# v2_full_project.net
KiCad netlist of a schematic drawn in EasyEDA Pro
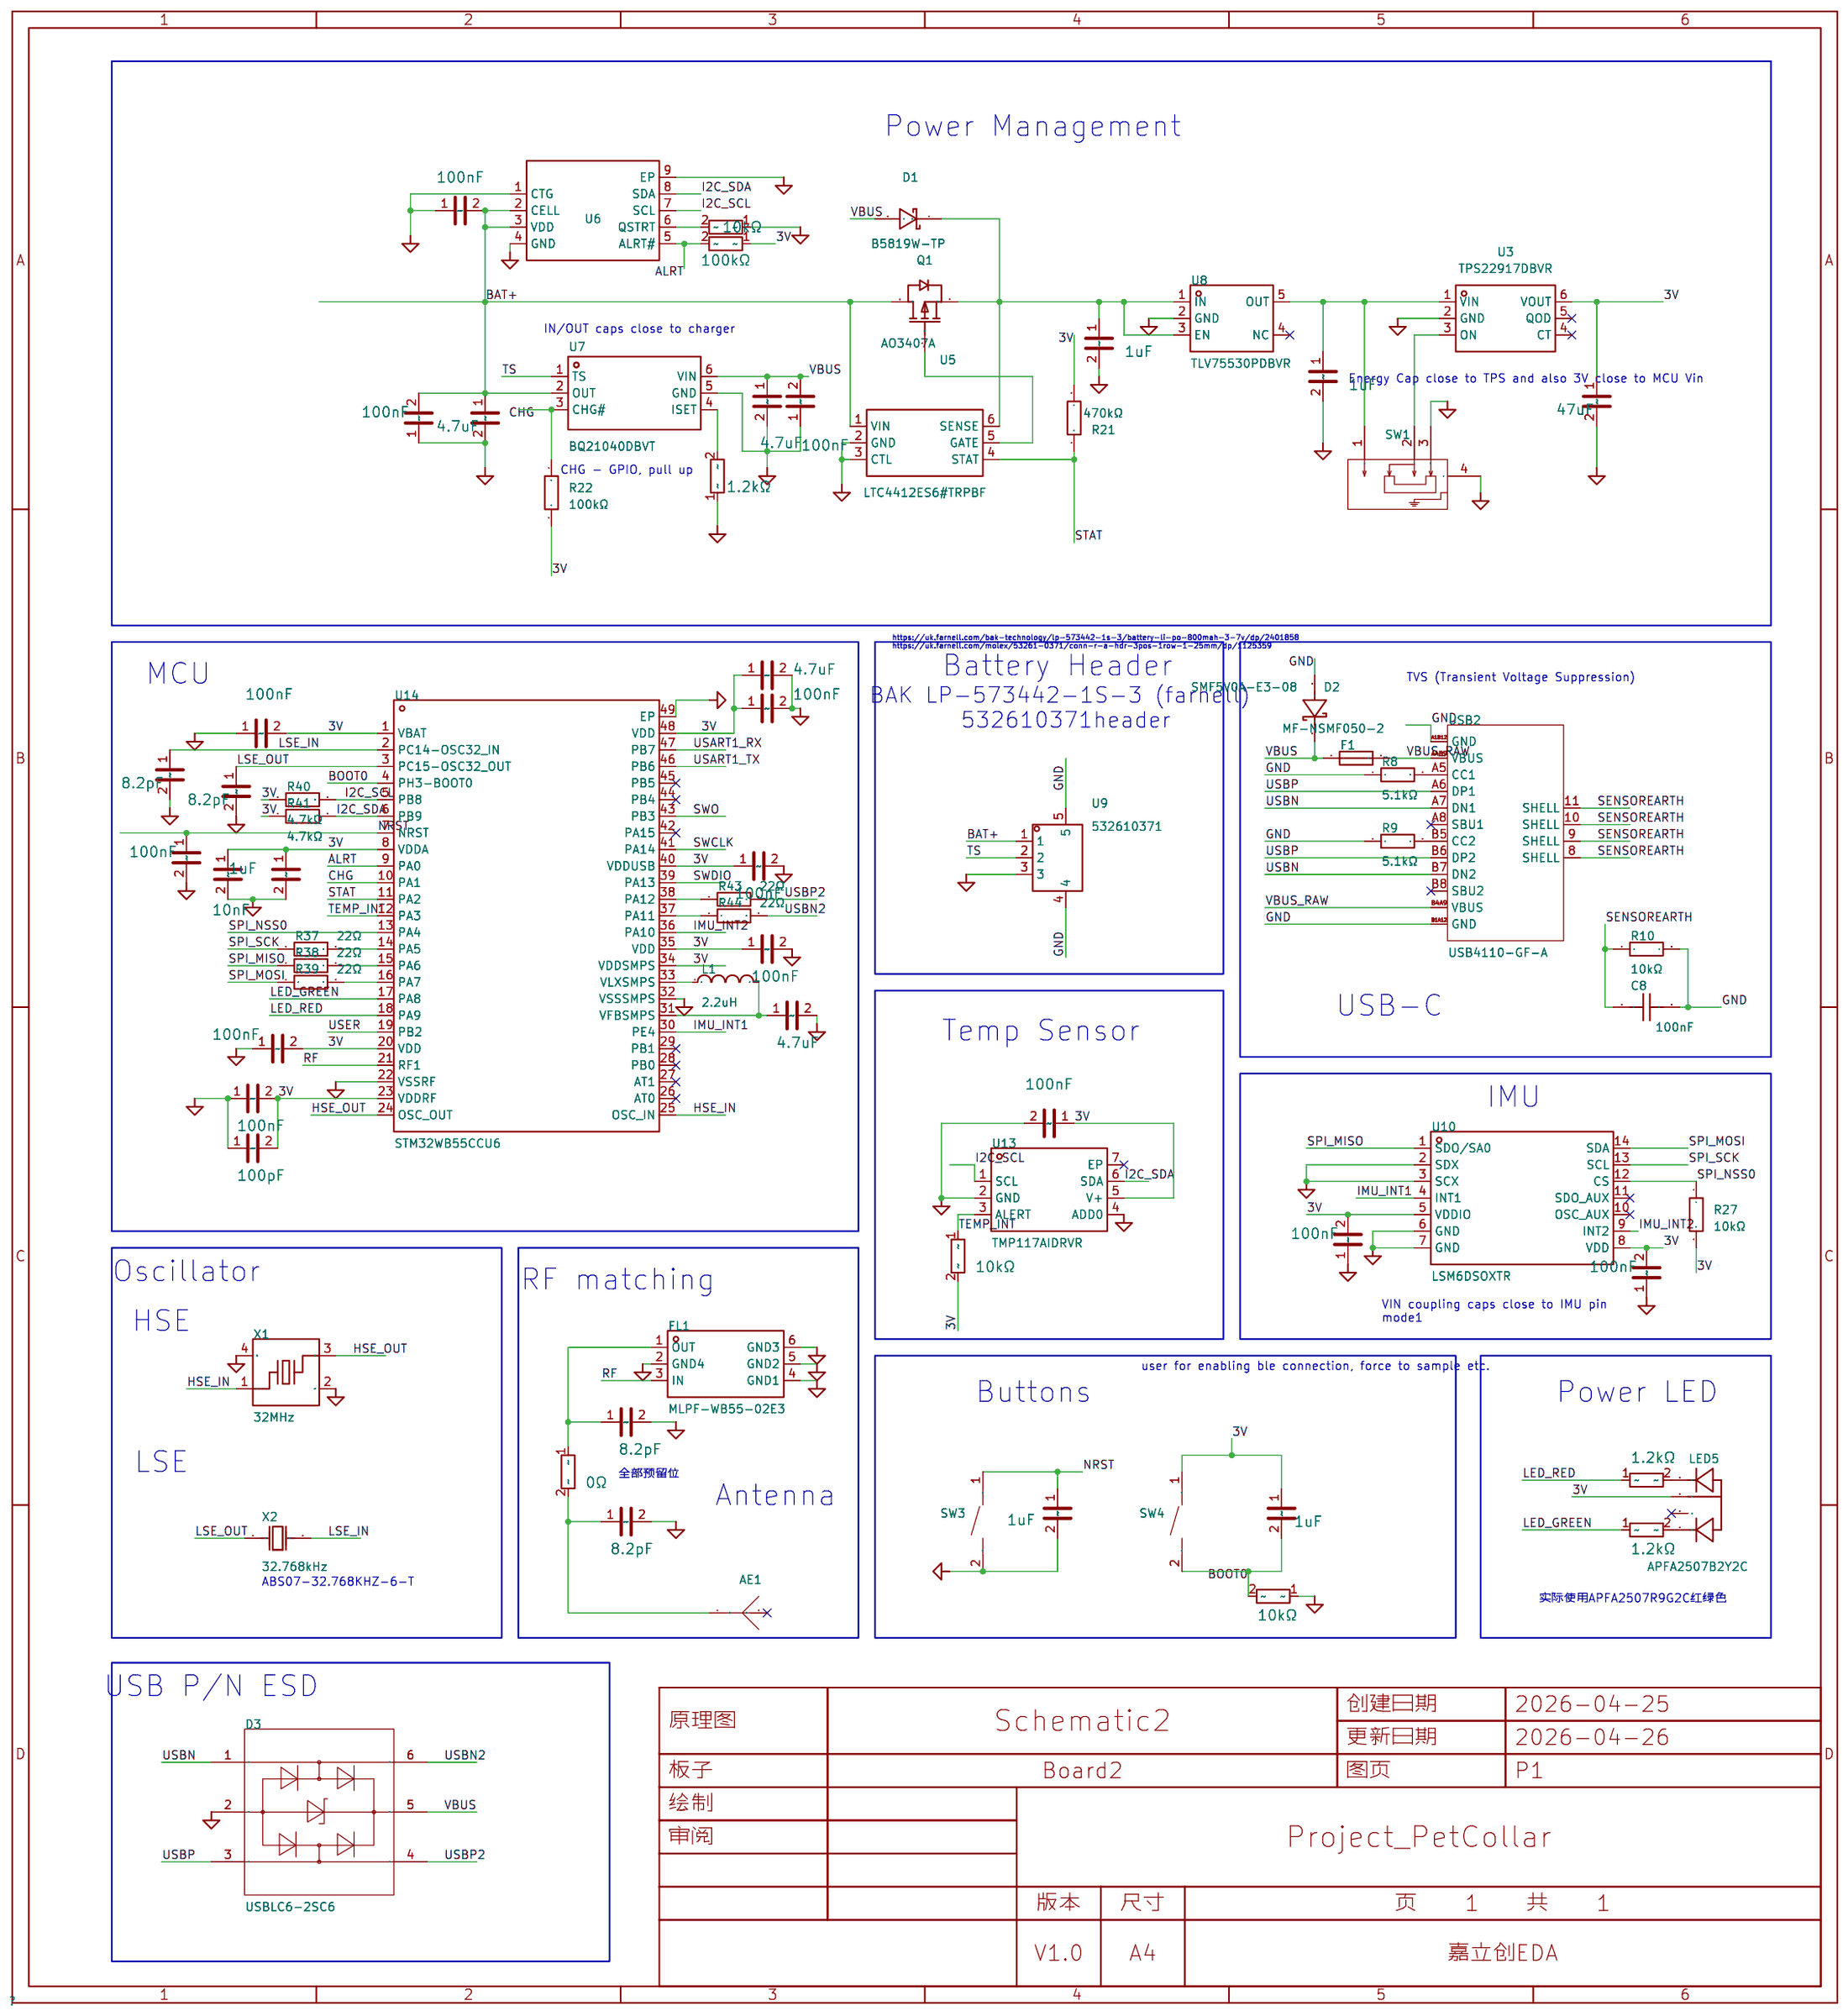
[diagram p0: schematic sheet]

(export (version "E")
  (design (tool "Eeschema 10.0.6"))
  (components
    (comp (ref "AE1")
      (value "2450AT18A100E")
      (footprint "easyedapro:ANT-SMD_L3.2-W1.6")
      (fields (field (name "Manufacturer") "JOHANSON(约翰逊)"))
      (libsource (lib "easyedapro") (part "2450AT18A100E"))
    )
    (comp (ref "C1")
      (value "100nF")
      (description "容值:100nF;精度:±10%;额定电压:50V;温度系数:X7R;")
      (fields
        (field (name "Manufacturer Part") "CL10B104KB8NNNC")
        (field (name "Manufacturer") "SAMSUNG(三星)")
      )
      (libsource (lib "easyedapro") (part "Device_C"))
    )
    (comp (ref "C2")
      (value "1uF")
      (description "容值:1uF;精度:±10%;额定电压:25V;温度系数:X7R;")
      (fields
        (field (name "Manufacturer Part") "CL10B105KA8NNNC")
        (field (name "Manufacturer") "SAMSUNG(三星)")
      )
      (libsource (lib "easyedapro") (part "Device_C"))
    )
    (comp (ref "C3")
      (value "1uF")
      (description "容值:1uF;精度:±10%;额定电压:25V;温度系数:X7R;")
      (fields
        (field (name "Manufacturer Part") "CL10B105KA8NNNC")
        (field (name "Manufacturer") "SAMSUNG(三星)")
      )
      (libsource (lib "easyedapro") (part "Device_C"))
    )
    (comp (ref "C5")
      (value "47uF")
      (description "容值:47uF;精度:±20%;额定电压:6.3V;温度系数:X5R;")
      (fields
        (field (name "Manufacturer Part") "CL21A476MQYNNNE")
        (field (name "Manufacturer") "SAMSUNG(三星)")
      )
      (libsource (lib "easyedapro") (part "Device_C"))
    )
    (comp (ref "C8")
      (value "100nF")
      (fields
        (field (name "Manufacturer Part") "CL10B104KB8NNNC")
        (field (name "Manufacturer") "SAMSUNG(三星)")
      )
      (libsource (lib "easyedapro") (part "Capacitance"))
    )
    (comp (ref "C19")
      (value "1uF")
      (description "容值:1uF;精度:±10%;额定电压:25V;温度系数:X7R;")
      (fields
        (field (name "Manufacturer Part") "CL10B105KA8NNNC")
        (field (name "Manufacturer") "SAMSUNG(三星)")
      )
      (libsource (lib "easyedapro") (part "Device_C"))
    )
    (comp (ref "C23")
      (value "4.7uF")
      (description "容值:4.7uF;精度:±10%;额定电压:16V;温度系数:X5R;")
      (fields
        (field (name "Manufacturer Part") "CL10A475KO8NNNC")
        (field (name "Manufacturer") "SAMSUNG(三星)")
      )
      (libsource (lib "easyedapro") (part "Device_C"))
    )
    (comp (ref "C24")
      (value "4.7uF")
      (description "容值:4.7uF;精度:±10%;额定电压:16V;温度系数:X5R;")
      (fields
        (field (name "Manufacturer Part") "CL10A475KO8NNNC")
        (field (name "Manufacturer") "SAMSUNG(三星)")
      )
      (libsource (lib "easyedapro") (part "Device_C"))
    )
    (comp (ref "C25")
      (value "100nF")
      (description "容值:100nF;精度:±10%;额定电压:50V;温度系数:X7R;")
      (fields
        (field (name "Manufacturer Part") "CL10B104KB8NNNC")
        (field (name "Manufacturer") "SAMSUNG(三星)")
      )
      (libsource (lib "easyedapro") (part "Device_C"))
    )
    (comp (ref "C26")
      (value "100nF")
      (description "容值:100nF;精度:±10%;额定电压:50V;温度系数:X7R;")
      (fields
        (field (name "Manufacturer Part") "CL10B104KB8NNNC")
        (field (name "Manufacturer") "SAMSUNG(三星)")
      )
      (libsource (lib "easyedapro") (part "Device_C"))
    )
    (comp (ref "C27")
      (value "100nF")
      (description "容值:100nF;精度:±10%;额定电压:50V;温度系数:X7R;")
      (fields
        (field (name "Manufacturer Part") "CL10B104KB8NNNC")
        (field (name "Manufacturer") "SAMSUNG(三星)")
      )
      (libsource (lib "easyedapro") (part "Device_C"))
    )
    (comp (ref "C28")
      (value "100nF")
      (description "容值:100nF;精度:±10%;额定电压:50V;温度系数:X7R;")
      (fields
        (field (name "Manufacturer Part") "CL10B104KB8NNNC")
        (field (name "Manufacturer") "SAMSUNG(三星)")
      )
      (libsource (lib "easyedapro") (part "Device_C"))
    )
    (comp (ref "C41")
      (value "100nF")
      (description "容值:100nF;精度:±10%;额定电压:50V;温度系数:X7R;")
      (fields
        (field (name "Manufacturer Part") "CL10B104KB8NNNC")
        (field (name "Manufacturer") "SAMSUNG(三星)")
      )
      (libsource (lib "easyedapro") (part "Device_C"))
    )
    (comp (ref "C42")
      (value "8.2pF")
      (description "容值:8.2pF;额定电压:50V;材质(温度系数):C0G;")
      (fields
        (field (name "Manufacturer Part") "GJM1555C1H8R2BB01D")
        (field (name "Manufacturer") "muRata(村田)")
      )
      (libsource (lib "easyedapro") (part "Device_C"))
    )
    (comp (ref "C43")
      (value "8.2pF")
      (description "容值:8.2pF;额定电压:50V;材质(温度系数):C0G;")
      (fields
        (field (name "Manufacturer Part") "GJM1555C1H8R2BB01D")
        (field (name "Manufacturer") "muRata(村田)")
      )
      (libsource (lib "easyedapro") (part "Device_C"))
    )
    (comp (ref "C46")
      (value "4.7uF")
      (description "容值:4.7uF;精度:±10%;额定电压:16V;温度系数:X5R;")
      (fields
        (field (name "Manufacturer Part") "CL10A475KO8NNNC")
        (field (name "Manufacturer") "SAMSUNG(三星)")
      )
      (libsource (lib "easyedapro") (part "Device_C"))
    )
    (comp (ref "C49")
      (value "100nF")
      (description "容值:100nF;精度:±10%;额定电压:50V;温度系数:X7R;")
      (fields
        (field (name "Manufacturer Part") "CL10B104KB8NNNC")
        (field (name "Manufacturer") "SAMSUNG(三星)")
      )
      (libsource (lib "easyedapro") (part "Device_C"))
    )
    (comp (ref "C50")
      (value "100nF")
      (description "容值:100nF;精度:±10%;额定电压:50V;温度系数:X7R;")
      (fields
        (field (name "Manufacturer Part") "CL10B104KB8NNNC")
        (field (name "Manufacturer") "SAMSUNG(三星)")
      )
      (libsource (lib "easyedapro") (part "Device_C"))
    )
    (comp (ref "C51")
      (value "100nF")
      (description "容值:100nF;精度:±10%;额定电压:50V;温度系数:X7R;")
      (fields
        (field (name "Manufacturer Part") "CL10B104KB8NNNC")
        (field (name "Manufacturer") "SAMSUNG(三星)")
      )
      (libsource (lib "easyedapro") (part "Device_C"))
    )
    (comp (ref "C52")
      (value "4.7uF")
      (description "容值:4.7uF;精度:±10%;额定电压:16V;温度系数:X5R;")
      (fields
        (field (name "Manufacturer Part") "CL10A475KO8NNNC")
        (field (name "Manufacturer") "SAMSUNG(三星)")
      )
      (libsource (lib "easyedapro") (part "Device_C"))
    )
    (comp (ref "C53")
      (value "10nF")
      (description "容值:10nF;精度:±5%;额定电压:50V;材质(温度系数):C0G;")
      (fields
        (field (name "Manufacturer Part") "GRM1885C1H103JA01D")
        (field (name "Manufacturer") "muRata(村田)")
      )
      (libsource (lib "easyedapro") (part "Device_C"))
    )
    (comp (ref "C54")
      (value "1uF")
      (description "容值:1uF;精度:±10%;额定电压:25V;温度系数:X7R;")
      (fields
        (field (name "Manufacturer Part") "CL10B105KA8NNNC")
        (field (name "Manufacturer") "SAMSUNG(三星)")
      )
      (libsource (lib "easyedapro") (part "Device_C"))
    )
    (comp (ref "C55")
      (value "100nF")
      (description "容值:100nF;精度:±10%;额定电压:50V;温度系数:X7R;")
      (fields
        (field (name "Manufacturer Part") "CL10B104KB8NNNC")
        (field (name "Manufacturer") "SAMSUNG(三星)")
      )
      (libsource (lib "easyedapro") (part "Device_C"))
    )
    (comp (ref "C56")
      (value "100nF")
      (description "容值:100nF;精度:±10%;额定电压:50V;温度系数:X7R;")
      (fields
        (field (name "Manufacturer Part") "CL10B104KB8NNNC")
        (field (name "Manufacturer") "SAMSUNG(三星)")
      )
      (libsource (lib "easyedapro") (part "Device_C"))
    )
    (comp (ref "C57")
      (value "100pF")
      (description "容值:100pF;精度:±5%;额定电压:50V;温度系数:C0G;")
      (fields
        (field (name "Manufacturer Part") "CL10C101JB8NNNC")
        (field (name "Manufacturer") "SAMSUNG(三星)")
      )
      (libsource (lib "easyedapro") (part "Device_C"))
    )
    (comp (ref "C58")
      (value "100nF")
      (description "容值:100nF;精度:±10%;额定电压:50V;温度系数:X7R;")
      (fields
        (field (name "Manufacturer Part") "CL10B104KB8NNNC")
        (field (name "Manufacturer") "SAMSUNG(三星)")
      )
      (libsource (lib "easyedapro") (part "Device_C"))
    )
    (comp (ref "C59")
      (value "100nF")
      (description "容值:100nF;精度:±10%;额定电压:50V;温度系数:X7R;")
      (fields
        (field (name "Manufacturer Part") "CL10B104KB8NNNC")
        (field (name "Manufacturer") "SAMSUNG(三星)")
      )
      (libsource (lib "easyedapro") (part "Device_C"))
    )
    (comp (ref "C60")
      (value "1uF")
      (description "容值:1uF;精度:±10%;额定电压:25V;温度系数:X7R;")
      (fields
        (field (name "Manufacturer Part") "CL10B105KA8NNNC")
        (field (name "Manufacturer") "SAMSUNG(三星)")
      )
      (libsource (lib "easyedapro") (part "Device_C"))
    )
    (comp (ref "C61")
      (value "8.2pF")
      (description "容值:8.2pF;额定电压:50V;材质(温度系数):C0G;")
      (fields
        (field (name "Manufacturer Part") "GJM1555C1H8R2BB01D")
        (field (name "Manufacturer") "muRata(村田)")
      )
      (libsource (lib "easyedapro") (part "Device_C"))
    )
    (comp (ref "C62")
      (value "8.2pF")
      (description "容值:8.2pF;额定电压:50V;材质(温度系数):C0G;")
      (fields
        (field (name "Manufacturer Part") "GJM1555C1H8R2BB01D")
        (field (name "Manufacturer") "muRata(村田)")
      )
      (libsource (lib "easyedapro") (part "Device_C"))
    )
    (comp (ref "D1")
      (value "B5819W-TP")
      (footprint "easyedapro:SOD-123_L2.8-W1.8-LS3.7-RD")
      (description "二极管配置:-;正向压降(Vf):600mV@1A;直流反向耐压(Vr):40V;整流电流:1A;")
      (fields (field (name "Manufacturer") "MCC(美微科)"))
      (libsource (lib "easyedapro") (part "B5819W-TP"))
    )
    (comp (ref "D2")
      (value "SMF5V0A-E3-08")
      (footprint "easyedapro:SMF_L2.8-W1.8-LS3.7-RD")
      (fields (field (name "Manufacturer") "VISHAY(威世)"))
      (libsource (lib "easyedapro") (part "SMF5V0A-E3-08"))
    )
    (comp (ref "D3")
      (value "USBLC6-2SC6")
      (footprint "easyedapro:SOT-23-6_L2.9-W1.6-P0.95-LS2.8-BL")
      (description "极性:单向;反向截止电压(Vrwm):5.25V;钳位电压:17V;峰值脉冲电流(Ipp):5A;击穿电压:6V;")
      (fields (field (name "Manufacturer") "ST(意法半导体)"))
      (libsource (lib "easyedapro") (part "USBLC6-2SC6"))
    )
    (comp (ref "F1")
      (value "MF-NSMF050-2")
      (footprint "easyedapro:F1206")
      (fields (field (name "Manufacturer") "BOURNS"))
      (libsource (lib "easyedapro") (part "MF-NSMF050-2"))
    )
    (comp (ref "FL1")
      (value "MLPF-WB55-02E3")
      (footprint "easyedapro:FILTER-SMD_6P-L1.6-W1.0-P0.50-BL")
      (fields (field (name "Manufacturer") "ST(意法半导体)"))
      (libsource (lib "easyedapro") (part "MLPF-WB55-02E3"))
    )
    (comp (ref "L1")
      (value "2.2uH")
      (footprint "easyedapro:L1008")
      (fields
        (field (name "Manufacturer Part") "1239AS-H-2R2M=P2")
        (field (name "Manufacturer") "muRata(村田)")
      )
      (libsource (lib "easyedapro") (part "1239AS-H-2R2M=P2"))
    )
    (comp (ref "LED5")
      (value "APFA2507B2Y2C")
      (footprint "easyedapro:LED-SMD_4P-L2.5-W1.0_APFA2507LQBDSEEZGKC")
      (fields (field (name "Manufacturer") "Kingbright"))
      (libsource (lib "easyedapro") (part "APFA2507B2Y2C"))
    )
    (comp (ref "Q1")
      (value "AO3407A")
      (footprint "easyedapro:SOT-23-3_L2.9-W1.6-P1.90-LS2.8-BR")
      (fields (field (name "Manufacturer") "AOS"))
      (libsource (lib "easyedapro") (part "AO3407A"))
    )
    (comp (ref "R1")
      (value "10kΩ")
      (description "电阻类型:厚膜电阻;阻值:10kΩ;精度:±1%;功率:100mW;最大工作电压:75V;温度系数:±100ppm/℃;")
      (fields (field (name "Manufacturer Part") "RC0603FR-0710KL") (field (name "Manufacturer") "YAGEO(国巨)"))
      (libsource (lib "easyedapro") (part "Device_R"))
    )
    (comp (ref "R2")
      (value "100kΩ")
      (description "电阻类型:厚膜电阻;阻值:100kΩ;精度:±1%;功率:100mW;最大工作电压:75V;温度系数:±100ppm/℃;")
      (fields (field (name "Manufacturer Part") "RC0603FR-07100KL") (field (name "Manufacturer") "YAGEO(国巨)"))
      (libsource (lib "easyedapro") (part "Device_R"))
    )
    (comp (ref "R8")
      (value "5.1kΩ")
      (fields (field (name "Manufacturer Part") "FRC0603F5102TS") (field (name "Manufacturer") "FOJAN(富捷)"))
      (libsource (lib "easyedapro") (part "电阻"))
    )
    (comp (ref "R9")
      (value "5.1kΩ")
      (fields (field (name "Manufacturer Part") "FRC0603F5102TS") (field (name "Manufacturer") "FOJAN(富捷)"))
      (libsource (lib "easyedapro") (part "电阻"))
    )
    (comp (ref "R10")
      (value "10kΩ")
      (fields (field (name "Manufacturer Part") "RC0603FR-0710KL") (field (name "Manufacturer") "YAGEO(国巨)"))
      (libsource (lib "easyedapro") (part "电阻"))
    )
    (comp (ref "R20")
      (value "1.2kΩ")
      (fields (field (name "Manufacturer Part") "RC0603FR-071K2L") (field (name "Manufacturer") "YAGEO(国巨)"))
      (libsource (lib "easyedapro") (part "Device_R"))
    )
    (comp (ref "R21")
      (value "470kΩ")
      (fields (field (name "Manufacturer Part") "FRC0603F4703TS") (field (name "Manufacturer") "FOJAN(富捷)"))
      (libsource (lib "easyedapro") (part "电阻"))
    )
    (comp (ref "R22")
      (value "100kΩ")
      (fields (field (name "Manufacturer Part") "RC0603FR-07100KL") (field (name "Manufacturer") "YAGEO(国巨)"))
      (libsource (lib "easyedapro") (part "电阻"))
    )
    (comp (ref "R27")
      (value "10kΩ")
      (fields (field (name "Manufacturer Part") "RC0603FR-0710KL") (field (name "Manufacturer") "YAGEO(国巨)"))
      (libsource (lib "easyedapro") (part "电阻"))
    )
    (comp (ref "R35")
      (value "10kΩ")
      (description "电阻类型:厚膜电阻;阻值:10kΩ;精度:±1%;功率:100mW;最大工作电压:75V;温度系数:±100ppm/℃;")
      (fields (field (name "Manufacturer Part") "RC0603FR-0710KL") (field (name "Manufacturer") "YAGEO(国巨)"))
      (libsource (lib "easyedapro") (part "Device_R"))
    )
    (comp (ref "R36")
      (value "0Ω")
      (description "电阻类型:厚膜电阻;阻值:0Ω;精度:±1%;功率:62.5mW;工作电压:50V;温度系数:-;")
      (fields (field (name "Manufacturer Part") "RC0402FR-070RL") (field (name "Manufacturer") "YAGEO(国巨)"))
      (libsource (lib "easyedapro") (part "Device_R"))
    )
    (comp (ref "R37")
      (value "22Ω")
      (fields (field (name "Manufacturer Part") "FRC0603J220 TS") (field (name "Manufacturer") "FOJAN(富捷)"))
      (libsource (lib "easyedapro") (part "电阻"))
    )
    (comp (ref "R38")
      (value "22Ω")
      (fields (field (name "Manufacturer Part") "FRC0603J220 TS") (field (name "Manufacturer") "FOJAN(富捷)"))
      (libsource (lib "easyedapro") (part "电阻"))
    )
    (comp (ref "R39")
      (value "22Ω")
      (fields (field (name "Manufacturer Part") "FRC0603J220 TS") (field (name "Manufacturer") "FOJAN(富捷)"))
      (libsource (lib "easyedapro") (part "电阻"))
    )
    (comp (ref "R40")
      (value "4.7kΩ")
      (fields (field (name "Manufacturer Part") "RC0603FR-074K7L") (field (name "Manufacturer") "YAGEO(国巨)"))
      (libsource (lib "easyedapro") (part "电阻"))
    )
    (comp (ref "R41")
      (value "4.7kΩ")
      (fields (field (name "Manufacturer Part") "RC0603FR-074K7L") (field (name "Manufacturer") "YAGEO(国巨)"))
      (libsource (lib "easyedapro") (part "电阻"))
    )
    (comp (ref "R42")
      (value "10kΩ")
      (description "电阻类型:厚膜电阻;阻值:10kΩ;精度:±1%;功率:100mW;最大工作电压:75V;温度系数:±100ppm/℃;")
      (fields (field (name "Manufacturer Part") "RC0603FR-0710KL") (field (name "Manufacturer") "YAGEO(国巨)"))
      (libsource (lib "easyedapro") (part "Device_R"))
    )
    (comp (ref "R43")
      (value "22Ω")
      (fields (field (name "Manufacturer Part") "FRC0603J220 TS") (field (name "Manufacturer") "FOJAN(富捷)"))
      (libsource (lib "easyedapro") (part "电阻"))
    )
    (comp (ref "R44")
      (value "22Ω")
      (fields (field (name "Manufacturer Part") "FRC0603J220 TS") (field (name "Manufacturer") "FOJAN(富捷)"))
      (libsource (lib "easyedapro") (part "电阻"))
    )
    (comp (ref "R45")
      (value "1.2kΩ")
      (fields (field (name "Manufacturer Part") "RC0603FR-071K2L") (field (name "Manufacturer") "YAGEO(国巨)"))
      (libsource (lib "easyedapro") (part "Device_R"))
    )
    (comp (ref "R46")
      (value "1.2kΩ")
      (fields (field (name "Manufacturer Part") "RC0603FR-071K2L") (field (name "Manufacturer") "YAGEO(国巨)"))
      (libsource (lib "easyedapro") (part "Device_R"))
    )
    (comp (ref "SW1")
      (value "MSK12C02")
      (footprint "easyedapro:SW-TH_MSK12C02")
      (fields (field (name "Manufacturer") "SHOU HAN(首韩)"))
      (libsource (lib "easyedapro") (part "MSK12C02"))
    )
    (comp (ref "SW3")
      (value "TS-1088-AR02016")
      (footprint "easyedapro:SW-SMD_L3.9-W3.0-P4.45")
      (fields (field (name "Manufacturer") "XUNPU(讯普)"))
      (libsource (lib "easyedapro") (part "TS-1088-AR02016"))
    )
    (comp (ref "SW4")
      (value "TS-1088-AR02016")
      (footprint "easyedapro:SW-SMD_L3.9-W3.0-P4.45")
      (fields (field (name "Manufacturer") "XUNPU(讯普)"))
      (libsource (lib "easyedapro") (part "TS-1088-AR02016"))
    )
    (comp (ref "U3")
      (value "TPS22917DBVR")
      (footprint "easyedapro:SOT-23-6_L2.9-W1.6-P0.95-LS2.8-BR")
      (description "类型:负载开关;通道数:1;输入控制逻辑:高电平有效;最大连续电流:2A;工作电压:0V~5.5V;导通电阻:80mΩ;")
      (fields (field (name "Manufacturer") "TI(德州仪器)"))
      (libsource (lib "easyedapro") (part "TPS22917DBVR"))
    )
    (comp (ref "U5")
      (value "LTC4412ES6#TRPBF")
      (footprint "easyedapro:TSOT-23-6_L2.9-W1.6-P0.95-LS2.8-BR")
      (description "负载类型:MOSFET;工作电压:2.5V~28V;")
      (fields (field (name "Manufacturer") "ADI(亚德诺)"))
      (libsource (lib "easyedapro") (part "LTC4412ES6#TRPBF"))
    )
    (comp (ref "U6")
      (value "MAX17048G+T10")
      (footprint "easyedapro:TDFN-8_L2.0-W2.0-P0.50-BL-EP1.2")
      (description "工作电压:2.5V~4.5V;电池类型:锂离子/聚合物;电池节数:1;")
      (fields (field (name "Manufacturer") "ADI(亚德诺)/MAXIM(美信)"))
      (libsource (lib "easyedapro") (part "MAX17048G+T10"))
    )
    (comp (ref "U7")
      (value "BQ21040DBVT")
      (footprint "easyedapro:SOT-23-6_L2.9-W1.6-P0.95-LS2.8-BR")
      (fields (field (name "Manufacturer") "TI(德州仪器)"))
      (libsource (lib "easyedapro") (part "BQ21040DBVT"))
    )
    (comp (ref "U8")
      (value "TLV75530PDBVR")
      (footprint "easyedapro:SOT-23-5_L3.0-W1.7-P0.95-LS2.8-BR")
      (fields (field (name "Manufacturer") "TI(德州仪器)"))
      (libsource (lib "easyedapro") (part "TLV75530PDBVR"))
    )
    (comp (ref "U9")
      (value "532610371")
      (footprint "easyedapro:CONN-TH_532610371")
      (fields (field (name "Manufacturer") "MOLEX"))
      (libsource (lib "easyedapro") (part "532610371"))
    )
    (comp (ref "U10")
      (value "LSM6DSOXTR")
      (footprint "easyedapro:LGA-14L_L3.0-W2.5-P0.50-TL")
      (fields (field (name "Manufacturer") "ST(意法半导体)"))
      (libsource (lib "easyedapro") (part "LSM6DSOXTR"))
    )
    (comp (ref "U13")
      (value "TMP117AIDRVR")
      (footprint "easyedapro:WSON-6_L2.0-W2.0-P0.65-TL-EP")
      (fields (field (name "Manufacturer") "TI(德州仪器)"))
      (libsource (lib "easyedapro") (part "TMP117AIDRVR"))
    )
    (comp (ref "U14")
      (value "STM32WB55CCU6")
      (footprint "easyedapro:VQFN-48_L7.0-W7.0-P0.50-BL-EP5.5")
      (fields (field (name "Manufacturer") "ST(意法半导体)"))
      (libsource (lib "easyedapro") (part "STM32WB55CCU6"))
    )
    (comp (ref "USB2")
      (value "USB4110-GF-A")
      (footprint "easyedapro:USB-C-SMD_TYPE-C-16P-USB4110-GF-A")
      (description "连接器类型:Type-C;协议标准:USB 2.0;公母:母;安装方式:卧贴;端口数量:1;额定电流 - 电源:5A;工作温度:-40°C~+85°C;")
      (fields (field (name "Manufacturer") "GCT"))
      (libsource (lib "easyedapro") (part "USB4110-GF-A"))
    )
    (comp (ref "X1")
      (value "32MHz")
      (footprint "easyedapro:CRYSTAL-SMD_4P-L2.0-W1.6-BL")
      (fields
        (field (name "Manufacturer Part") "NX2016SA-32MHZ-EXS00A-CS06654")
        (field (name "Manufacturer") "NDK")
      )
      (libsource (lib "easyedapro") (part "NX2016SA-32MHZ-EXS00A-CS06654"))
    )
    (comp (ref "X2")
      (value "32.768kHz")
      (footprint "easyedapro:CRYSTAL-SMD_L3.2-W1.5-2")
      (fields
        (field (name "Manufacturer Part") "ABS07-32.768KHZ-6-T")
        (field (name "Manufacturer") "ABRACON")
      )
      (libsource (lib "easyedapro") (part "ABS07-32.768KHZ-6-T"))
    )
  )
  (nets
    (net (code "1") (name "/3V") (class "Default")
      (node (ref "C27") (pin "2") (pinfunction "~_2") (pintype "unspecified"))
      (node (ref "C28") (pin "2") (pinfunction "~_2") (pintype "unspecified"))
      (node (ref "C41") (pin "1") (pinfunction "~_1") (pintype "unspecified"))
      (node (ref "C49") (pin "2") (pinfunction "~_2") (pintype "unspecified"))
      (node (ref "C5") (pin "1") (pinfunction "~_1") (pintype "unspecified"))
      (node (ref "C50") (pin "1") (pinfunction "~_1") (pintype "unspecified"))
      (node (ref "C51") (pin "1") (pinfunction "~_1") (pintype "unspecified"))
      (node (ref "C52") (pin "1") (pinfunction "~_1") (pintype "unspecified"))
      (node (ref "C53") (pin "1") (pinfunction "~_1") (pintype "unspecified"))
      (node (ref "C54") (pin "1") (pinfunction "~_1") (pintype "unspecified"))
      (node (ref "C55") (pin "1") (pinfunction "~_1") (pintype "unspecified"))
      (node (ref "C56") (pin "2") (pinfunction "~_2") (pintype "unspecified"))
      (node (ref "C57") (pin "2") (pinfunction "~_2") (pintype "unspecified"))
      (node (ref "C58") (pin "2") (pinfunction "~_2") (pintype "unspecified"))
      (node (ref "C60") (pin "1") (pinfunction "~_1") (pintype "unspecified"))
      (node (ref "LED5") (pin "2") (pinfunction "2_2") (pintype "unspecified"))
      (node (ref "R2") (pin "1") (pinfunction "~_1") (pintype "unspecified"))
      (node (ref "R21") (pin "2") (pinfunction "2_2") (pintype "input"))
      (node (ref "R22") (pin "2") (pinfunction "2_2") (pintype "input"))
      (node (ref "R27") (pin "2") (pinfunction "2_2") (pintype "input"))
      (node (ref "R35") (pin "2") (pinfunction "~_2") (pintype "unspecified"))
      (node (ref "R40") (pin "1") (pinfunction "1_1") (pintype "input"))
      (node (ref "R41") (pin "1") (pinfunction "1_1") (pintype "input"))
      (node (ref "SW4") (pin "1") (pinfunction "1_1") (pintype "unspecified"))
      (node (ref "U10") (pin "5") (pinfunction "VDDIO_5") (pintype "unspecified"))
      (node (ref "U10") (pin "8") (pinfunction "VDD_8") (pintype "unspecified"))
      (node (ref "U13") (pin "5") (pinfunction "V+_5") (pintype "unspecified"))
      (node (ref "U14") (pin "1") (pinfunction "VBAT_1") (pintype "unspecified"))
      (node (ref "U14") (pin "20") (pinfunction "VDD_20") (pintype "unspecified"))
      (node (ref "U14") (pin "23") (pinfunction "VDDRF_23") (pintype "unspecified"))
      (node (ref "U14") (pin "34") (pinfunction "VDDSMPS_34") (pintype "unspecified"))
      (node (ref "U14") (pin "35") (pinfunction "VDD_35") (pintype "unspecified"))
      (node (ref "U14") (pin "40") (pinfunction "VDDUSB_40") (pintype "unspecified"))
      (node (ref "U14") (pin "48") (pinfunction "VDD_48") (pintype "unspecified"))
      (node (ref "U14") (pin "8") (pinfunction "VDDA_8") (pintype "unspecified"))
      (node (ref "U3") (pin "6") (pinfunction "VOUT_6") (pintype "unspecified"))
    )
    (net (code "2") (name "/ALRT") (class "Default")
      (node (ref "R2") (pin "2") (pinfunction "~_2") (pintype "unspecified"))
      (node (ref "U14") (pin "9") (pinfunction "PA0_9") (pintype "unspecified"))
      (node (ref "U6") (pin "5") (pinfunction "ALRT#_5") (pintype "unspecified"))
    )
    (net (code "3") (name "/BAT+") (class "Default")
      (node (ref "C1") (pin "2") (pinfunction "~_2") (pintype "unspecified"))
      (node (ref "C24") (pin "1") (pinfunction "~_1") (pintype "unspecified"))
      (node (ref "C25") (pin "2") (pinfunction "~_2") (pintype "unspecified"))
      (node (ref "Q1") (pin "3") (pinfunction "D_3") (pintype "unspecified"))
      (node (ref "U5") (pin "1") (pinfunction "VIN_1") (pintype "unspecified"))
      (node (ref "U6") (pin "2") (pinfunction "CELL_2") (pintype "unspecified"))
      (node (ref "U6") (pin "3") (pinfunction "VDD_3") (pintype "unspecified"))
      (node (ref "U7") (pin "2") (pinfunction "OUT_2") (pintype "unspecified"))
      (node (ref "U9") (pin "1") (pinfunction "1_1") (pintype "unspecified"))
    )
    (net (code "4") (name "/BOOT0") (class "Default")
      (node (ref "C60") (pin "2") (pinfunction "~_2") (pintype "unspecified"))
      (node (ref "R42") (pin "2") (pinfunction "~_2") (pintype "unspecified"))
      (node (ref "SW4") (pin "2") (pinfunction "2_2") (pintype "unspecified"))
      (node (ref "U14") (pin "4") (pinfunction "PH3-BOOT0_4") (pintype "unspecified"))
    )
    (net (code "5") (name "/CHG") (class "Default")
      (node (ref "R22") (pin "1") (pinfunction "1_1") (pintype "input"))
      (node (ref "U14") (pin "10") (pinfunction "PA1_10") (pintype "unspecified"))
      (node (ref "U7") (pin "3") (pinfunction "CHG#_3") (pintype "unspecified"))
    )
    (net (code "6") (name "/HSE_IN") (class "Default")
      (node (ref "U14") (pin "25") (pinfunction "OSC_IN_25") (pintype "unspecified"))
      (node (ref "X1") (pin "1") (pinfunction "1_1") (pintype "input"))
    )
    (net (code "7") (name "/HSE_OUT") (class "Default")
      (node (ref "U14") (pin "24") (pinfunction "OSC_OUT_24") (pintype "unspecified"))
      (node (ref "X1") (pin "3") (pinfunction "3_3") (pintype "input"))
    )
    (net (code "8") (name "/I2C_SCL") (class "Default")
      (node (ref "R40") (pin "2") (pinfunction "2_2") (pintype "input"))
      (node (ref "U13") (pin "1") (pinfunction "SCL_1") (pintype "unspecified"))
      (node (ref "U14") (pin "5") (pinfunction "PB8_5") (pintype "unspecified"))
      (node (ref "U6") (pin "7") (pinfunction "SCL_7") (pintype "unspecified"))
    )
    (net (code "9") (name "/I2C_SDA") (class "Default")
      (node (ref "R41") (pin "2") (pinfunction "2_2") (pintype "input"))
      (node (ref "U13") (pin "6") (pinfunction "SDA_6") (pintype "unspecified"))
      (node (ref "U14") (pin "6") (pinfunction "PB9_6") (pintype "unspecified"))
      (node (ref "U6") (pin "8") (pinfunction "SDA_8") (pintype "unspecified"))
    )
    (net (code "10") (name "/IMU_INT1") (class "Default")
      (node (ref "U10") (pin "4") (pinfunction "INT1_4") (pintype "unspecified"))
      (node (ref "U14") (pin "30") (pinfunction "PE4_30") (pintype "unspecified"))
    )
    (net (code "11") (name "/IMU_INT2") (class "Default")
      (node (ref "U10") (pin "9") (pinfunction "INT2_9") (pintype "unspecified"))
      (node (ref "U14") (pin "36") (pinfunction "PA10_36") (pintype "unspecified"))
    )
    (net (code "12") (name "/LED_GREEN") (class "Default")
      (node (ref "R46") (pin "1") (pinfunction "~_1") (pintype "unspecified"))
      (node (ref "U14") (pin "17") (pinfunction "PA8_17") (pintype "unspecified"))
    )
    (net (code "13") (name "/LED_RED") (class "Default")
      (node (ref "R45") (pin "1") (pinfunction "~_1") (pintype "unspecified"))
      (node (ref "U14") (pin "18") (pinfunction "PA9_18") (pintype "unspecified"))
    )
    (net (code "14") (name "/LSE_IN") (class "Default")
      (node (ref "C42") (pin "1") (pinfunction "~_1") (pintype "unspecified"))
      (node (ref "U14") (pin "2") (pinfunction "PC14-OSC32_IN_2") (pintype "unspecified"))
      (node (ref "X2") (pin "2") (pinfunction "OSC2_2") (pintype "input"))
    )
    (net (code "15") (name "/LSE_OUT") (class "Default")
      (node (ref "C43") (pin "1") (pinfunction "~_1") (pintype "unspecified"))
      (node (ref "U14") (pin "3") (pinfunction "PC15-OSC32_OUT_3") (pintype "unspecified"))
      (node (ref "X2") (pin "1") (pinfunction "OSC1_1") (pintype "input"))
    )
    (net (code "16") (name "/NRST") (class "Default")
      (node (ref "C19") (pin "1") (pinfunction "~_1") (pintype "unspecified"))
      (node (ref "C59") (pin "1") (pinfunction "~_1") (pintype "unspecified"))
      (node (ref "SW3") (pin "1") (pinfunction "1_1") (pintype "unspecified"))
      (node (ref "U14") (pin "7") (pinfunction "NRST_7") (pintype "unspecified"))
    )
    (net (code "17") (name "/RF") (class "Default")
      (node (ref "FL1") (pin "3") (pinfunction "IN_3") (pintype "unspecified"))
      (node (ref "U14") (pin "21") (pinfunction "RF1_21") (pintype "unspecified"))
    )
    (net (code "18") (name "/SENSOREARTH") (class "Default")
      (node (ref "C8") (pin "1") (pinfunction "1_1") (pintype "input"))
      (node (ref "R10") (pin "1") (pinfunction "1_1") (pintype "input"))
      (node (ref "USB2") (pin "10") (pinfunction "SHELL_10") (pintype "unspecified"))
      (node (ref "USB2") (pin "11") (pinfunction "SHELL_11") (pintype "unspecified"))
      (node (ref "USB2") (pin "8") (pinfunction "SHELL_8") (pintype "unspecified"))
      (node (ref "USB2") (pin "9") (pinfunction "SHELL_9") (pintype "unspecified"))
    )
    (net (code "19") (name "/SPI_MISO") (class "Default")
      (node (ref "R38") (pin "1") (pinfunction "1_1") (pintype "input"))
      (node (ref "U10") (pin "1") (pinfunction "SDO/SA0_1") (pintype "unspecified"))
    )
    (net (code "20") (name "/SPI_MOSI") (class "Default")
      (node (ref "R39") (pin "1") (pinfunction "1_1") (pintype "input"))
      (node (ref "U10") (pin "14") (pinfunction "SDA_14") (pintype "unspecified"))
    )
    (net (code "21") (name "/SPI_NSS0") (class "Default")
      (node (ref "R27") (pin "1") (pinfunction "1_1") (pintype "input"))
      (node (ref "U10") (pin "12") (pinfunction "CS_12") (pintype "unspecified"))
      (node (ref "U14") (pin "13") (pinfunction "PA4_13") (pintype "unspecified"))
    )
    (net (code "22") (name "/SPI_SCK") (class "Default")
      (node (ref "R37") (pin "1") (pinfunction "1_1") (pintype "input"))
      (node (ref "U10") (pin "13") (pinfunction "SCL_13") (pintype "unspecified"))
    )
    (net (code "23") (name "/STAT") (class "Default")
      (node (ref "R21") (pin "1") (pinfunction "1_1") (pintype "input"))
      (node (ref "U14") (pin "11") (pinfunction "PA2_11") (pintype "unspecified"))
      (node (ref "U5") (pin "4") (pinfunction "STAT_4") (pintype "unspecified"))
    )
    (net (code "24") (name "/SWCLK") (class "Default")
      (node (ref "U14") (pin "41") (pinfunction "PA14_41") (pintype "unspecified"))
    )
    (net (code "25") (name "/SWDIO") (class "Default")
      (node (ref "U14") (pin "39") (pinfunction "PA13_39") (pintype "unspecified"))
    )
    (net (code "26") (name "/SWO") (class "Default")
      (node (ref "U14") (pin "43") (pinfunction "PB3_43") (pintype "unspecified"))
    )
    (net (code "27") (name "/TEMP_INT") (class "Default")
      (node (ref "R35") (pin "1") (pinfunction "~_1") (pintype "unspecified"))
      (node (ref "U13") (pin "3") (pinfunction "ALERT_3") (pintype "unspecified"))
      (node (ref "U14") (pin "12") (pinfunction "PA3_12") (pintype "unspecified"))
    )
    (net (code "28") (name "/TS") (class "Default")
      (node (ref "U7") (pin "1") (pinfunction "TS_1") (pintype "unspecified"))
      (node (ref "U9") (pin "2") (pinfunction "2_2") (pintype "unspecified"))
    )
    (net (code "29") (name "/USART1_RX") (class "Default")
      (node (ref "U14") (pin "47") (pinfunction "PB7_47") (pintype "unspecified"))
    )
    (net (code "30") (name "/USART1_TX") (class "Default")
      (node (ref "U14") (pin "46") (pinfunction "PB6_46") (pintype "unspecified"))
    )
    (net (code "31") (name "/USBN") (class "Default")
      (node (ref "D3") (pin "1") (pinfunction "1_1") (pintype "input"))
      (node (ref "USB2") (pin "A7") (pinfunction "DN1_A7") (pintype "unspecified"))
      (node (ref "USB2") (pin "B7") (pinfunction "DN2_B7") (pintype "unspecified"))
    )
    (net (code "32") (name "/USBN2") (class "Default")
      (node (ref "D3") (pin "6") (pinfunction "6_6") (pintype "input"))
      (node (ref "R44") (pin "2") (pinfunction "2_2") (pintype "input"))
    )
    (net (code "33") (name "/USBP") (class "Default")
      (node (ref "D3") (pin "3") (pinfunction "3_3") (pintype "input"))
      (node (ref "USB2") (pin "A6") (pinfunction "DP1_A6") (pintype "unspecified"))
      (node (ref "USB2") (pin "B6") (pinfunction "DP2_B6") (pintype "unspecified"))
    )
    (net (code "34") (name "/USBP2") (class "Default")
      (node (ref "D3") (pin "4") (pinfunction "4_4") (pintype "input"))
      (node (ref "R43") (pin "2") (pinfunction "2_2") (pintype "input"))
    )
    (net (code "35") (name "/USER") (class "Default")
      (node (ref "U14") (pin "19") (pinfunction "PB2_19") (pintype "unspecified"))
    )
    (net (code "36") (name "/VBUS") (class "Default")
      (node (ref "C23") (pin "1") (pinfunction "~_1") (pintype "unspecified"))
      (node (ref "C26") (pin "2") (pinfunction "~_2") (pintype "unspecified"))
      (node (ref "D1") (pin "2") (pinfunction "A_2") (pintype "unspecified"))
      (node (ref "D2") (pin "1") (pinfunction "K_1") (pintype "unspecified"))
      (node (ref "D3") (pin "5") (pinfunction "5_5") (pintype "input"))
      (node (ref "F1") (pin "1") (pinfunction "1_1") (pintype "unspecified"))
      (node (ref "U7") (pin "6") (pinfunction "VIN_6") (pintype "unspecified"))
    )
    (net (code "37") (name "/VBUS_RAW") (class "Default")
      (node (ref "F1") (pin "2") (pinfunction "2_2") (pintype "unspecified"))
      (node (ref "USB2") (pin "A4B9") (pinfunction "VBUS_A4B9") (pintype "unspecified"))
      (node (ref "USB2") (pin "B4A9") (pinfunction "VBUS_B4A9") (pintype "unspecified"))
    )
    (net (code "38") (name "GND") (class "Default")
      (node (ref "C1") (pin "1") (pinfunction "~_1") (pintype "unspecified"))
      (node (ref "C19") (pin "2") (pinfunction "~_2") (pintype "unspecified"))
      (node (ref "C2") (pin "2") (pinfunction "~_2") (pintype "unspecified"))
      (node (ref "C23") (pin "2") (pinfunction "~_2") (pintype "unspecified"))
      (node (ref "C24") (pin "2") (pinfunction "~_2") (pintype "unspecified"))
      (node (ref "C25") (pin "1") (pinfunction "~_1") (pintype "unspecified"))
      (node (ref "C26") (pin "1") (pinfunction "~_1") (pintype "unspecified"))
      (node (ref "C27") (pin "1") (pinfunction "~_1") (pintype "unspecified"))
      (node (ref "C28") (pin "1") (pinfunction "~_1") (pintype "unspecified"))
      (node (ref "C3") (pin "2") (pinfunction "~_2") (pintype "unspecified"))
      (node (ref "C41") (pin "2") (pinfunction "~_2") (pintype "unspecified"))
      (node (ref "C42") (pin "2") (pinfunction "~_2") (pintype "unspecified"))
      (node (ref "C43") (pin "2") (pinfunction "~_2") (pintype "unspecified"))
      (node (ref "C46") (pin "2") (pinfunction "~_2") (pintype "unspecified"))
      (node (ref "C49") (pin "1") (pinfunction "~_1") (pintype "unspecified"))
      (node (ref "C5") (pin "2") (pinfunction "~_2") (pintype "unspecified"))
      (node (ref "C50") (pin "2") (pinfunction "~_2") (pintype "unspecified"))
      (node (ref "C51") (pin "2") (pinfunction "~_2") (pintype "unspecified"))
      (node (ref "C52") (pin "2") (pinfunction "~_2") (pintype "unspecified"))
      (node (ref "C53") (pin "2") (pinfunction "~_2") (pintype "unspecified"))
      (node (ref "C54") (pin "2") (pinfunction "~_2") (pintype "unspecified"))
      (node (ref "C55") (pin "2") (pinfunction "~_2") (pintype "unspecified"))
      (node (ref "C56") (pin "1") (pinfunction "~_1") (pintype "unspecified"))
      (node (ref "C57") (pin "1") (pinfunction "~_1") (pintype "unspecified"))
      (node (ref "C58") (pin "1") (pinfunction "~_1") (pintype "unspecified"))
      (node (ref "C59") (pin "2") (pinfunction "~_2") (pintype "unspecified"))
      (node (ref "C61") (pin "2") (pinfunction "~_2") (pintype "unspecified"))
      (node (ref "C62") (pin "2") (pinfunction "~_2") (pintype "unspecified"))
      (node (ref "C8") (pin "2") (pinfunction "2_2") (pintype "input"))
      (node (ref "D2") (pin "2") (pinfunction "A_2") (pintype "unspecified"))
      (node (ref "D3") (pin "2") (pinfunction "2_2") (pintype "input"))
      (node (ref "FL1") (pin "2") (pinfunction "GND4_2") (pintype "unspecified"))
      (node (ref "FL1") (pin "4") (pinfunction "GND1_4") (pintype "unspecified"))
      (node (ref "FL1") (pin "5") (pinfunction "GND2_5") (pintype "unspecified"))
      (node (ref "FL1") (pin "6") (pinfunction "GND3_6") (pintype "unspecified"))
      (node (ref "R1") (pin "1") (pinfunction "~_1") (pintype "unspecified"))
      (node (ref "R10") (pin "2") (pinfunction "2_2") (pintype "input"))
      (node (ref "R20") (pin "1") (pinfunction "~_1") (pintype "unspecified"))
      (node (ref "R42") (pin "1") (pinfunction "~_1") (pintype "unspecified"))
      (node (ref "R8") (pin "1") (pinfunction "1_1") (pintype "input"))
      (node (ref "R9") (pin "1") (pinfunction "1_1") (pintype "input"))
      (node (ref "SW1") (pin "3") (pinfunction "3_3") (pintype "unspecified"))
      (node (ref "SW1") (pin "4") (pinfunction "4_4") (pintype "unspecified"))
      (node (ref "SW3") (pin "2") (pinfunction "2_2") (pintype "unspecified"))
      (node (ref "U10") (pin "2") (pinfunction "SDX_2") (pintype "unspecified"))
      (node (ref "U10") (pin "3") (pinfunction "SCX_3") (pintype "unspecified"))
      (node (ref "U10") (pin "6") (pinfunction "GND_6") (pintype "unspecified"))
      (node (ref "U10") (pin "7") (pinfunction "GND_7") (pintype "unspecified"))
      (node (ref "U13") (pin "2") (pinfunction "GND_2") (pintype "unspecified"))
      (node (ref "U13") (pin "4") (pinfunction "ADD0_4") (pintype "unspecified"))
      (node (ref "U14") (pin "22") (pinfunction "VSSRF_22") (pintype "unspecified"))
      (node (ref "U14") (pin "32") (pinfunction "VSSSMPS_32") (pintype "unspecified"))
      (node (ref "U14") (pin "49") (pinfunction "EP_49") (pintype "unspecified"))
      (node (ref "U3") (pin "2") (pinfunction "GND_2") (pintype "unspecified"))
      (node (ref "U5") (pin "2") (pinfunction "GND_2") (pintype "unspecified"))
      (node (ref "U5") (pin "3") (pinfunction "CTL_3") (pintype "unspecified"))
      (node (ref "U6") (pin "1") (pinfunction "CTG_1") (pintype "unspecified"))
      (node (ref "U6") (pin "4") (pinfunction "GND_4") (pintype "unspecified"))
      (node (ref "U6") (pin "9") (pinfunction "EP_9") (pintype "unspecified"))
      (node (ref "U7") (pin "5") (pinfunction "GND_5") (pintype "unspecified"))
      (node (ref "U8") (pin "2") (pinfunction "GND_2") (pintype "unspecified"))
      (node (ref "U9") (pin "3") (pinfunction "3_3") (pintype "unspecified"))
      (node (ref "U9") (pin "4") (pinfunction "4_4") (pintype "unspecified"))
      (node (ref "U9") (pin "5") (pinfunction "5_5") (pintype "unspecified"))
      (node (ref "USB2") (pin "A1B12") (pinfunction "GND_A1B12") (pintype "unspecified"))
      (node (ref "USB2") (pin "B1A12") (pinfunction "GND_B1A12") (pintype "unspecified"))
      (node (ref "X1") (pin "2") (pinfunction "GND_2") (pintype "input"))
      (node (ref "X1") (pin "4") (pinfunction "GND_4") (pintype "input"))
    )
    (net (code "39") (name "Net-(AE1-ANT)") (class "Default")
      (node (ref "AE1") (pin "1") (pinfunction "ANT_1") (pintype "unspecified"))
      (node (ref "C62") (pin "1") (pinfunction "~_1") (pintype "unspecified"))
      (node (ref "R36") (pin "2") (pinfunction "~_2") (pintype "unspecified"))
    )
    (net (code "40") (name "Net-(D1-C)") (class "Default")
      (node (ref "C2") (pin "1") (pinfunction "~_1") (pintype "unspecified"))
      (node (ref "D1") (pin "1") (pinfunction "C_1") (pintype "unspecified"))
      (node (ref "Q1") (pin "2") (pinfunction "S_2") (pintype "unspecified"))
      (node (ref "U5") (pin "6") (pinfunction "SENSE_6") (pintype "unspecified"))
      (node (ref "U8") (pin "1") (pinfunction "IN_1") (pintype "unspecified"))
      (node (ref "U8") (pin "3") (pinfunction "EN_3") (pintype "unspecified"))
    )
    (net (code "41") (name "Net-(FL1-OUT)") (class "Default")
      (node (ref "C61") (pin "1") (pinfunction "~_1") (pintype "unspecified"))
      (node (ref "FL1") (pin "1") (pinfunction "OUT_1") (pintype "unspecified"))
      (node (ref "R36") (pin "1") (pinfunction "~_1") (pintype "unspecified"))
    )
    (net (code "42") (name "Net-(LED5-Pad1)") (class "Default")
      (node (ref "LED5") (pin "1") (pinfunction "1_1") (pintype "unspecified"))
      (node (ref "R45") (pin "2") (pinfunction "~_2") (pintype "unspecified"))
    )
    (net (code "43") (name "Net-(LED5-Pad4)") (class "Default")
      (node (ref "LED5") (pin "4") (pinfunction "4_4") (pintype "unspecified"))
      (node (ref "R46") (pin "2") (pinfunction "~_2") (pintype "unspecified"))
    )
    (net (code "44") (name "Net-(Q1-G)") (class "Default")
      (node (ref "Q1") (pin "1") (pinfunction "G_1") (pintype "unspecified"))
      (node (ref "U5") (pin "5") (pinfunction "GATE_5") (pintype "unspecified"))
    )
    (net (code "45") (name "Net-(U3-ON)") (class "Default")
      (node (ref "SW1") (pin "2") (pinfunction "2_2") (pintype "unspecified"))
      (node (ref "U3") (pin "3") (pinfunction "ON_3") (pintype "unspecified"))
    )
    (net (code "46") (name "Net-(U3-VIN)") (class "Default")
      (node (ref "C3") (pin "1") (pinfunction "~_1") (pintype "unspecified"))
      (node (ref "SW1") (pin "1") (pinfunction "1_1") (pintype "unspecified"))
      (node (ref "U3") (pin "1") (pinfunction "VIN_1") (pintype "unspecified"))
      (node (ref "U8") (pin "5") (pinfunction "OUT_5") (pintype "unspecified"))
    )
    (net (code "47") (name "Net-(U6-QSTRT)") (class "Default")
      (node (ref "R1") (pin "2") (pinfunction "~_2") (pintype "unspecified"))
      (node (ref "U6") (pin "6") (pinfunction "QSTRT_6") (pintype "unspecified"))
    )
    (net (code "48") (name "Net-(U7-ISET)") (class "Default")
      (node (ref "R20") (pin "2") (pinfunction "~_2") (pintype "unspecified"))
      (node (ref "U7") (pin "4") (pinfunction "ISET_4") (pintype "unspecified"))
    )
    (net (code "49") (name "Net-(U14-PA5)") (class "Default")
      (node (ref "R37") (pin "2") (pinfunction "2_2") (pintype "input"))
      (node (ref "U14") (pin "14") (pinfunction "PA5_14") (pintype "unspecified"))
    )
    (net (code "50") (name "Net-(U14-PA6)") (class "Default")
      (node (ref "R38") (pin "2") (pinfunction "2_2") (pintype "input"))
      (node (ref "U14") (pin "15") (pinfunction "PA6_15") (pintype "unspecified"))
    )
    (net (code "51") (name "Net-(U14-PA7)") (class "Default")
      (node (ref "R39") (pin "2") (pinfunction "2_2") (pintype "input"))
      (node (ref "U14") (pin "16") (pinfunction "PA7_16") (pintype "unspecified"))
    )
    (net (code "52") (name "Net-(U14-PA11)") (class "Default")
      (node (ref "R44") (pin "1") (pinfunction "1_1") (pintype "input"))
      (node (ref "U14") (pin "37") (pinfunction "PA11_37") (pintype "unspecified"))
    )
    (net (code "53") (name "Net-(U14-PA12)") (class "Default")
      (node (ref "R43") (pin "1") (pinfunction "1_1") (pintype "input"))
      (node (ref "U14") (pin "38") (pinfunction "PA12_38") (pintype "unspecified"))
    )
    (net (code "54") (name "Net-(U14-VFBSMPS)") (class "Default")
      (node (ref "C46") (pin "1") (pinfunction "~_1") (pintype "unspecified"))
      (node (ref "L1") (pin "2") (pinfunction "2_2") (pintype "unspecified"))
      (node (ref "U14") (pin "31") (pinfunction "VFBSMPS_31") (pintype "unspecified"))
    )
    (net (code "55") (name "Net-(U14-VLXSMPS)") (class "Default")
      (node (ref "L1") (pin "1") (pinfunction "1_1") (pintype "unspecified"))
      (node (ref "U14") (pin "33") (pinfunction "VLXSMPS_33") (pintype "unspecified"))
    )
    (net (code "56") (name "Net-(USB2-CC1)") (class "Default")
      (node (ref "R8") (pin "2") (pinfunction "2_2") (pintype "input"))
      (node (ref "USB2") (pin "A5") (pinfunction "CC1_A5") (pintype "unspecified"))
    )
    (net (code "57") (name "Net-(USB2-CC2)") (class "Default")
      (node (ref "R9") (pin "2") (pinfunction "2_2") (pintype "input"))
      (node (ref "USB2") (pin "B5") (pinfunction "CC2_B5") (pintype "unspecified"))
    )
    (net (code "58") (name "unconnected-(AE1-Pad2)") (class "Default")
      (node (ref "AE1") (pin "2") (pinfunction "2_2") (pintype "unspecified+no_connect"))
    )
    (net (code "59") (name "unconnected-(LED5-Pad3)") (class "Default")
      (node (ref "LED5") (pin "3") (pinfunction "3_3") (pintype "unspecified+no_connect"))
    )
    (net (code "60") (name "unconnected-(U3-CT-Pad4)") (class "Default")
      (node (ref "U3") (pin "4") (pinfunction "CT_4") (pintype "unspecified+no_connect"))
    )
    (net (code "61") (name "unconnected-(U3-QOD-Pad5)") (class "Default")
      (node (ref "U3") (pin "5") (pinfunction "QOD_5") (pintype "unspecified+no_connect"))
    )
    (net (code "62") (name "unconnected-(U8-NC-Pad4)") (class "Default")
      (node (ref "U8") (pin "4") (pinfunction "NC_4") (pintype "unspecified+no_connect"))
    )
    (net (code "63") (name "unconnected-(U10-OSC_AUX-Pad10)") (class "Default")
      (node (ref "U10") (pin "10") (pinfunction "OSC_AUX_10") (pintype "unspecified+no_connect"))
    )
    (net (code "64") (name "unconnected-(U10-SDO_AUX-Pad11)") (class "Default")
      (node (ref "U10") (pin "11") (pinfunction "SDO_AUX_11") (pintype "unspecified+no_connect"))
    )
    (net (code "65") (name "unconnected-(U13-EP-Pad7)") (class "Default")
      (node (ref "U13") (pin "7") (pinfunction "EP_7") (pintype "unspecified+no_connect"))
    )
    (net (code "66") (name "unconnected-(U14-AT0-Pad26)") (class "Default")
      (node (ref "U14") (pin "26") (pinfunction "AT0_26") (pintype "unspecified+no_connect"))
    )
    (net (code "67") (name "unconnected-(U14-AT1-Pad27)") (class "Default")
      (node (ref "U14") (pin "27") (pinfunction "AT1_27") (pintype "unspecified+no_connect"))
    )
    (net (code "68") (name "unconnected-(U14-PA15-Pad42)") (class "Default")
      (node (ref "U14") (pin "42") (pinfunction "PA15_42") (pintype "unspecified+no_connect"))
    )
    (net (code "69") (name "unconnected-(U14-PB0-Pad28)") (class "Default")
      (node (ref "U14") (pin "28") (pinfunction "PB0_28") (pintype "unspecified+no_connect"))
    )
    (net (code "70") (name "unconnected-(U14-PB1-Pad29)") (class "Default")
      (node (ref "U14") (pin "29") (pinfunction "PB1_29") (pintype "unspecified+no_connect"))
    )
    (net (code "71") (name "unconnected-(U14-PB4-Pad44)") (class "Default")
      (node (ref "U14") (pin "44") (pinfunction "PB4_44") (pintype "unspecified+no_connect"))
    )
    (net (code "72") (name "unconnected-(U14-PB5-Pad45)") (class "Default")
      (node (ref "U14") (pin "45") (pinfunction "PB5_45") (pintype "unspecified+no_connect"))
    )
    (net (code "73") (name "unconnected-(USB2-SBU1-PadA8)") (class "Default")
      (node (ref "USB2") (pin "A8") (pinfunction "SBU1_A8") (pintype "unspecified+no_connect"))
    )
    (net (code "74") (name "unconnected-(USB2-SBU2-PadB8)") (class "Default")
      (node (ref "USB2") (pin "B8") (pinfunction "SBU2_B8") (pintype "unspecified+no_connect"))
    )
  )
)
